# controlboard.net
KiCad netlist of a schematic drawn in EAGLE
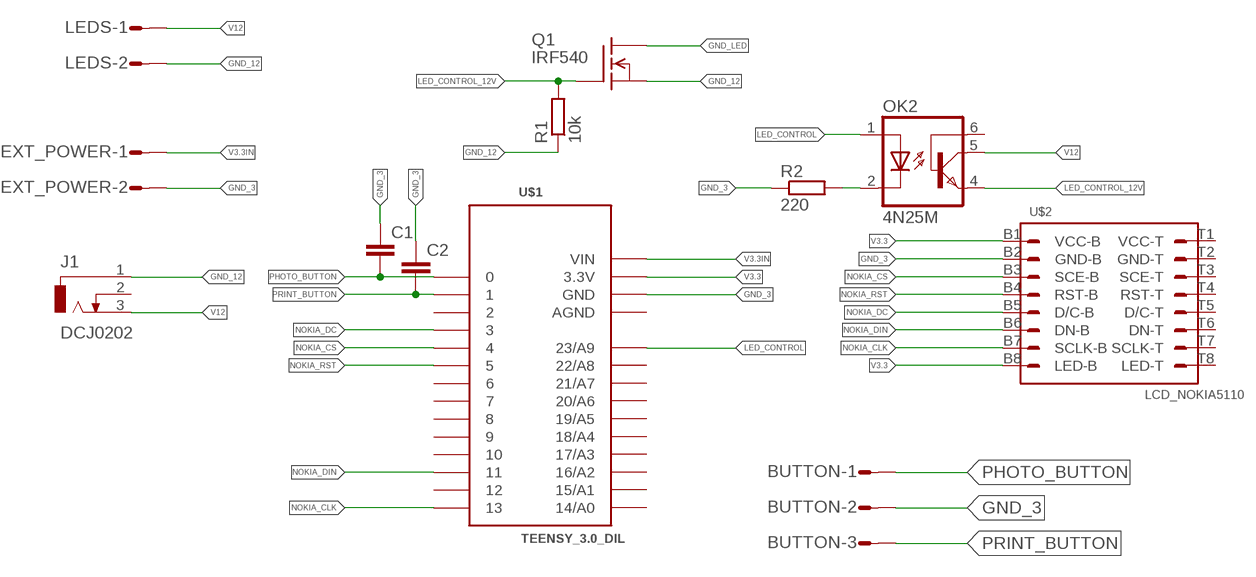
[diagram p0: schematic, sheet 1]

(export (version "E")
  (design (tool "Eeschema 10.0.6"))
  (components
    (comp (ref "BUTTON")
      (value "L03P")
      (footprint "eagle-import:L03P")
      (libsource (lib "eagle-import") (part "L03P"))
    )
    (comp (ref "C1")
      (value "C-EU025-025X050")
      (footprint "eagle-import:C025-025X050")
      (libsource (lib "eagle-import") (part "C-EU025-025X050"))
    )
    (comp (ref "C2")
      (value "C-EU025-025X050")
      (footprint "eagle-import:C025-025X050")
      (libsource (lib "eagle-import") (part "C-EU025-025X050"))
    )
    (comp (ref "EXT_POWER")
      (value "S02P")
      (footprint "eagle-import:S02P")
      (libsource (lib "eagle-import") (part "S02P"))
    )
    (comp (ref "J1")
      (value "DCJ0202")
      (footprint "eagle-import:DCJ0202")
      (libsource (lib "eagle-import") (part "DCJ0202"))
    )
    (comp (ref "LEDS")
      (value "L02P")
      (footprint "eagle-import:L02P")
      (libsource (lib "eagle-import") (part "L02P"))
    )
    (comp (ref "OK2")
      (value "4N25M")
      (footprint "eagle-import:DIL06")
      (fields (field (name "MPN") "4N25-M"))
      (libsource (lib "eagle-import") (part "4N?M25"))
    )
    (comp (ref "Q1")
      (value "IRF540")
      (footprint "eagle-import:TO220")
      (libsource (lib "eagle-import") (part "IRF540"))
    )
    (comp (ref "R1")
      (value "10k")
      (footprint "eagle-import:0207_10")
      (libsource (lib "eagle-import") (part "R-EU_0207/10"))
    )
    (comp (ref "R2")
      (value "220")
      (footprint "eagle-import:0207_10")
      (libsource (lib "eagle-import") (part "resistor_R-EU_0207/10"))
    )
    (comp (ref "U$1")
      (value "TEENSY_3.0_DIL")
      (footprint "eagle-import:TEENSY3-DIL")
      (libsource (lib "eagle-import") (part "TEENSY_3.0_DIL"))
    )
    (comp (ref "U$2")
      (value "LCD_NOKIA5110")
      (footprint "eagle-import:NOKIA5110")
      (libsource (lib "eagle-import") (part "LCD_NOKIA5110"))
    )
  )
  (nets
    (net (code "1") (name "/AGND") (class "Default")
      (node (ref "U$1") (pin "AGND") (pinfunction "AGND_AGND") (pintype "power_in"))
    )
    (net (code "2") (name "GND_3") (class "Default")
      (node (ref "BUTTON") (pin "2") (pinfunction "S_2") (pintype "passive"))
      (node (ref "C1") (pin "1") (pinfunction "1_1") (pintype "passive"))
      (node (ref "C2") (pin "1") (pinfunction "1_1") (pintype "passive"))
      (node (ref "EXT_POWER") (pin "2") (pinfunction "S_2") (pintype "passive"))
      (node (ref "R2") (pin "1") (pinfunction "1_1") (pintype "passive"))
      (node (ref "U$1") (pin "GND") (pinfunction "GND_GND") (pintype "power_in"))
      (node (ref "U$2") (pin "B2") (pinfunction "GND-B_B2") (pintype "bidirectional"))
    )
    (net (code "3") (name "GND_12") (class "Default")
      (node (ref "J1") (pin "1") (pinfunction "1_1") (pintype "passive"))
      (node (ref "LEDS") (pin "2") (pinfunction "S_2") (pintype "passive"))
      (node (ref "Q1") (pin "3") (pinfunction "S_3") (pintype "passive"))
      (node (ref "R1") (pin "1") (pinfunction "1_1") (pintype "passive"))
    )
    (net (code "4") (name "GND_LED") (class "Default")
      (node (ref "Q1") (pin "2") (pinfunction "D_2") (pintype "passive"))
    )
    (net (code "5") (name "LED_CONTROL") (class "Default")
      (node (ref "OK2") (pin "1") (pinfunction "A_1") (pintype "passive"))
      (node (ref "U$1") (pin "23/A9") (pinfunction "23/A9_23/A9") (pintype "bidirectional"))
    )
    (net (code "6") (name "LED_CONTROL_12V") (class "Default")
      (node (ref "OK2") (pin "4") (pinfunction "EMI_4") (pintype "passive"))
      (node (ref "Q1") (pin "1") (pinfunction "G_1") (pintype "passive"))
      (node (ref "R1") (pin "2") (pinfunction "2_2") (pintype "passive"))
    )
    (net (code "7") (name "NOKIA_CLK") (class "Default")
      (node (ref "U$1") (pin "13") (pinfunction "13_13") (pintype "bidirectional"))
      (node (ref "U$2") (pin "B7") (pinfunction "SCLK-B_B7") (pintype "bidirectional"))
    )
    (net (code "8") (name "NOKIA_CS") (class "Default")
      (node (ref "U$1") (pin "4") (pinfunction "4_4") (pintype "bidirectional"))
      (node (ref "U$2") (pin "B3") (pinfunction "SCE-B_B3") (pintype "bidirectional"))
    )
    (net (code "9") (name "NOKIA_DC") (class "Default")
      (node (ref "U$1") (pin "3") (pinfunction "3_3") (pintype "bidirectional"))
      (node (ref "U$2") (pin "B5") (pinfunction "D/C-B_B5") (pintype "bidirectional"))
    )
    (net (code "10") (name "NOKIA_DIN") (class "Default")
      (node (ref "U$1") (pin "11") (pinfunction "11_11") (pintype "bidirectional"))
      (node (ref "U$2") (pin "B6") (pinfunction "DN-B_B6") (pintype "bidirectional"))
    )
    (net (code "11") (name "NOKIA_RST") (class "Default")
      (node (ref "U$1") (pin "5") (pinfunction "5_5") (pintype "bidirectional"))
      (node (ref "U$2") (pin "B4") (pinfunction "RST-B_B4") (pintype "bidirectional"))
    )
    (net (code "12") (name "Net-(OK2-C)") (class "Default")
      (node (ref "OK2") (pin "2") (pinfunction "C_2") (pintype "passive"))
      (node (ref "R2") (pin "2") (pinfunction "2_2") (pintype "passive"))
    )
    (net (code "13") (name "PHOTO_BUTTON") (class "Default")
      (node (ref "BUTTON") (pin "1") (pinfunction "S_1") (pintype "passive"))
      (node (ref "C1") (pin "2") (pinfunction "2_2") (pintype "passive"))
      (node (ref "U$1") (pin "0") (pinfunction "0_0") (pintype "bidirectional"))
    )
    (net (code "14") (name "PRINT_BUTTON") (class "Default")
      (node (ref "BUTTON") (pin "3") (pinfunction "S_3") (pintype "passive"))
      (node (ref "C2") (pin "2") (pinfunction "2_2") (pintype "passive"))
      (node (ref "U$1") (pin "1") (pinfunction "1_1") (pintype "bidirectional"))
    )
    (net (code "15") (name "V3.3") (class "Default")
      (node (ref "U$1") (pin "3.3V") (pinfunction "3.3V_3.3V") (pintype "power_in"))
      (node (ref "U$2") (pin "B1") (pinfunction "VCC-B_B1") (pintype "bidirectional"))
      (node (ref "U$2") (pin "B8") (pinfunction "LED-B_B8") (pintype "bidirectional"))
    )
    (net (code "16") (name "V3.3IN") (class "Default")
      (node (ref "EXT_POWER") (pin "1") (pinfunction "S_1") (pintype "passive"))
      (node (ref "U$1") (pin "VIN") (pinfunction "VIN_VIN") (pintype "power_in"))
    )
    (net (code "17") (name "V12") (class "Default")
      (node (ref "J1") (pin "3") (pinfunction "3_3") (pintype "passive"))
      (node (ref "LEDS") (pin "1") (pinfunction "S_1") (pintype "passive"))
      (node (ref "OK2") (pin "5") (pinfunction "COL_5") (pintype "passive"))
    )
    (net (code "18") (name "unconnected-(J1-Pad2)") (class "Default")
      (node (ref "J1") (pin "2") (pinfunction "2_2") (pintype "passive"))
    )
    (net (code "19") (name "unconnected-(OK2-BAS-Pad6)") (class "Default")
      (node (ref "OK2") (pin "6") (pinfunction "BAS_6") (pintype "passive"))
    )
    (net (code "20") (name "unconnected-(U$1-Pad2)") (class "Default")
      (node (ref "U$1") (pin "2") (pinfunction "2_2") (pintype "bidirectional"))
    )
    (net (code "21") (name "unconnected-(U$1-Pad6)") (class "Default")
      (node (ref "U$1") (pin "6") (pinfunction "6_6") (pintype "bidirectional"))
    )
    (net (code "22") (name "unconnected-(U$1-Pad7)") (class "Default")
      (node (ref "U$1") (pin "7") (pinfunction "7_7") (pintype "bidirectional"))
    )
    (net (code "23") (name "unconnected-(U$1-Pad8)") (class "Default")
      (node (ref "U$1") (pin "8") (pinfunction "8_8") (pintype "bidirectional"))
    )
    (net (code "24") (name "unconnected-(U$1-Pad9)") (class "Default")
      (node (ref "U$1") (pin "9") (pinfunction "9_9") (pintype "bidirectional"))
    )
    (net (code "25") (name "unconnected-(U$1-Pad10)") (class "Default")
      (node (ref "U$1") (pin "10") (pinfunction "10_10") (pintype "bidirectional"))
    )
    (net (code "26") (name "unconnected-(U$1-Pad12)") (class "Default")
      (node (ref "U$1") (pin "12") (pinfunction "12_12") (pintype "bidirectional"))
    )
    (net (code "27") (name "unconnected-(U$1-Pad14{slash}A0)") (class "Default")
      (node (ref "U$1") (pin "14/A0") (pinfunction "14/A0_14/A0") (pintype "bidirectional"))
    )
    (net (code "28") (name "unconnected-(U$1-Pad15{slash}A1)") (class "Default")
      (node (ref "U$1") (pin "15/A1") (pinfunction "15/A1_15/A1") (pintype "bidirectional"))
    )
    (net (code "29") (name "unconnected-(U$1-Pad16{slash}A2)") (class "Default")
      (node (ref "U$1") (pin "16/A2") (pinfunction "16/A2_16/A2") (pintype "bidirectional"))
    )
    (net (code "30") (name "unconnected-(U$1-Pad17{slash}A3)") (class "Default")
      (node (ref "U$1") (pin "17/A3") (pinfunction "17/A3_17/A3") (pintype "bidirectional"))
    )
    (net (code "31") (name "unconnected-(U$1-Pad18{slash}A4)") (class "Default")
      (node (ref "U$1") (pin "18/A4") (pinfunction "18/A4_18/A4") (pintype "bidirectional"))
    )
    (net (code "32") (name "unconnected-(U$1-Pad19{slash}A5)") (class "Default")
      (node (ref "U$1") (pin "19/A5") (pinfunction "19/A5_19/A5") (pintype "bidirectional"))
    )
    (net (code "33") (name "unconnected-(U$1-Pad20{slash}A6)") (class "Default")
      (node (ref "U$1") (pin "20/A6") (pinfunction "20/A6_20/A6") (pintype "bidirectional"))
    )
    (net (code "34") (name "unconnected-(U$1-Pad21{slash}A7)") (class "Default")
      (node (ref "U$1") (pin "21/A7") (pinfunction "21/A7_21/A7") (pintype "bidirectional"))
    )
    (net (code "35") (name "unconnected-(U$1-Pad22{slash}A8)") (class "Default")
      (node (ref "U$1") (pin "22/A8") (pinfunction "22/A8_22/A8") (pintype "bidirectional"))
    )
    (net (code "36") (name "unconnected-(U$2-DN-T-PadT6)") (class "Default")
      (node (ref "U$2") (pin "T6") (pinfunction "DN-T_T6") (pintype "bidirectional"))
    )
    (net (code "37") (name "unconnected-(U$2-D{slash}C-T-PadT5)") (class "Default")
      (node (ref "U$2") (pin "T5") (pinfunction "D/C-T_T5") (pintype "bidirectional"))
    )
    (net (code "38") (name "unconnected-(U$2-GND-T-PadT2)") (class "Default")
      (node (ref "U$2") (pin "T2") (pinfunction "GND-T_T2") (pintype "bidirectional"))
    )
    (net (code "39") (name "unconnected-(U$2-LED-T-PadT8)") (class "Default")
      (node (ref "U$2") (pin "T8") (pinfunction "LED-T_T8") (pintype "bidirectional"))
    )
    (net (code "40") (name "unconnected-(U$2-RST-T-PadT4)") (class "Default")
      (node (ref "U$2") (pin "T4") (pinfunction "RST-T_T4") (pintype "bidirectional"))
    )
    (net (code "41") (name "unconnected-(U$2-SCE-T-PadT3)") (class "Default")
      (node (ref "U$2") (pin "T3") (pinfunction "SCE-T_T3") (pintype "bidirectional"))
    )
    (net (code "42") (name "unconnected-(U$2-SCLK-T-PadT7)") (class "Default")
      (node (ref "U$2") (pin "T7") (pinfunction "SCLK-T_T7") (pintype "bidirectional"))
    )
    (net (code "43") (name "unconnected-(U$2-VCC-T-PadT1)") (class "Default")
      (node (ref "U$2") (pin "T1") (pinfunction "VCC-T_T1") (pintype "bidirectional"))
    )
  )
)
